# lab3_analog_input.net
KiCad netlist of a schematic drawn in Altium Designer
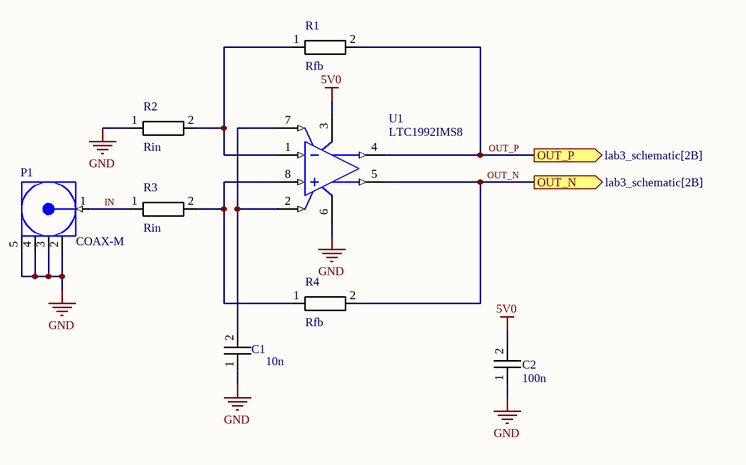
[diagram p0: lab3_analog_input.SchDoc]

(export (version "E")
  (design (tool "Eeschema 10.0.6"))
  (components
    (comp (ref "C1")
      (value "10n")
      (footprint "PcbLib_MW:0805_IPC")
      (libsource (lib "Schlib_MW") (part "Capacitor"))
    )
    (comp (ref "C2")
      (value "100n")
      (footprint "PcbLib_MW:0805_IPC")
      (libsource (lib "Schlib_MW") (part "Capacitor"))
    )
    (comp (ref "P1")
      (value "COAX-M")
      (footprint "MMCX2.54-V5")
      (description "RF Coaxial PCB Connector, MMCX; Thru-Hole, Vertical Mount Plug,  50 Ohm Impedance")
      (fields (field (name "PUBLISHER") "Altium Limited"))
      (libsource (lib "Miscellaneous Connectors") (part "COAX-M"))
    )
    (comp (ref "R1")
      (value "Rfb")
      (footprint "PcbLib_MW:0603")
      (libsource (lib "Schlib_MW") (part "Resistor"))
    )
    (comp (ref "R2")
      (value "Rin")
      (footprint "PcbLib_MW:0603")
      (libsource (lib "Schlib_MW") (part "Resistor"))
    )
    (comp (ref "R3")
      (value "Rin")
      (footprint "PcbLib_MW:0603")
      (libsource (lib "Schlib_MW") (part "Resistor"))
    )
    (comp (ref "R4")
      (value "Rfb")
      (footprint "PcbLib_MW:0603")
      (libsource (lib "Schlib_MW") (part "Resistor"))
    )
    (comp (ref "U1")
      (value "LTC1992IMS8")
      (footprint "PcbLib_MW:LT-MS8-8_L")
      (fields
        (field (name "LINEAR TECHNOLOGY PART NUMBER") "LTC1992")
        (field (name "MANUFACTURER") "Linear Technology")
      )
      (libsource (lib "Schlib_MW") (part "CMP-0359-00506-2"))
    )
  )
  (nets
    (net (code "1") (name "/IN") (class "Default")
      (node (ref "P1") (pin "1") (pinfunction "Signal_1") (pintype "input"))
      (node (ref "R3") (pin "1") (pinfunction "PIN_1") (pintype "passive"))
    )
    (net (code "2") (name "/OUT_N") (class "Default")
      (node (ref "R4") (pin "2") (pinfunction "PIN_2") (pintype "passive"))
      (node (ref "U1") (pin "5") (pinfunction "-OUT_5") (pintype "output"))
    )
    (net (code "3") (name "/OUT_P") (class "Default")
      (node (ref "R1") (pin "2") (pinfunction "PIN_2") (pintype "passive"))
      (node (ref "U1") (pin "4") (pinfunction "+OUT_4") (pintype "output"))
    )
    (net (code "4") (name "5V0") (class "Default")
      (node (ref "C2") (pin "2") (pinfunction "PIN_2") (pintype "passive"))
      (node (ref "U1") (pin "3") (pinfunction "+VS_3") (pintype "power_in"))
    )
    (net (code "5") (name "GND") (class "Default")
      (node (ref "C1") (pin "1") (pinfunction "PIN_1") (pintype "passive"))
      (node (ref "C2") (pin "1") (pinfunction "PIN_1") (pintype "passive"))
      (node (ref "P1") (pin "2") (pinfunction "GND_2") (pintype "power_in"))
      (node (ref "P1") (pin "3") (pinfunction "GND_3") (pintype "power_in"))
      (node (ref "P1") (pin "4") (pinfunction "GND_4") (pintype "power_in"))
      (node (ref "P1") (pin "5") (pinfunction "GND_5") (pintype "power_in"))
      (node (ref "R2") (pin "1") (pinfunction "PIN_1") (pintype "passive"))
      (node (ref "U1") (pin "6") (pinfunction "-VS_6") (pintype "power_in"))
    )
    (net (code "6") (name "Net-(U1-+IN)") (class "Default")
      (node (ref "R3") (pin "2") (pinfunction "PIN_2") (pintype "passive"))
      (node (ref "R4") (pin "1") (pinfunction "PIN_1") (pintype "passive"))
      (node (ref "U1") (pin "8") (pinfunction "+IN_8") (pintype "input"))
    )
    (net (code "7") (name "Net-(U1--IN)") (class "Default")
      (node (ref "R1") (pin "1") (pinfunction "PIN_1") (pintype "passive"))
      (node (ref "R2") (pin "2") (pinfunction "PIN_2") (pintype "passive"))
      (node (ref "U1") (pin "1") (pinfunction "-IN_1") (pintype "input"))
    )
    (net (code "8") (name "Net-(U1-VMID)") (class "Default")
      (node (ref "C1") (pin "2") (pinfunction "PIN_2") (pintype "passive"))
      (node (ref "U1") (pin "2") (pinfunction "VOCM_2") (pintype "input"))
      (node (ref "U1") (pin "7") (pinfunction "VMID_7") (pintype "input"))
    )
  )
)
